# RMII_Dongle.net
KiCad netlist of a schematic drawn in Altium Designer
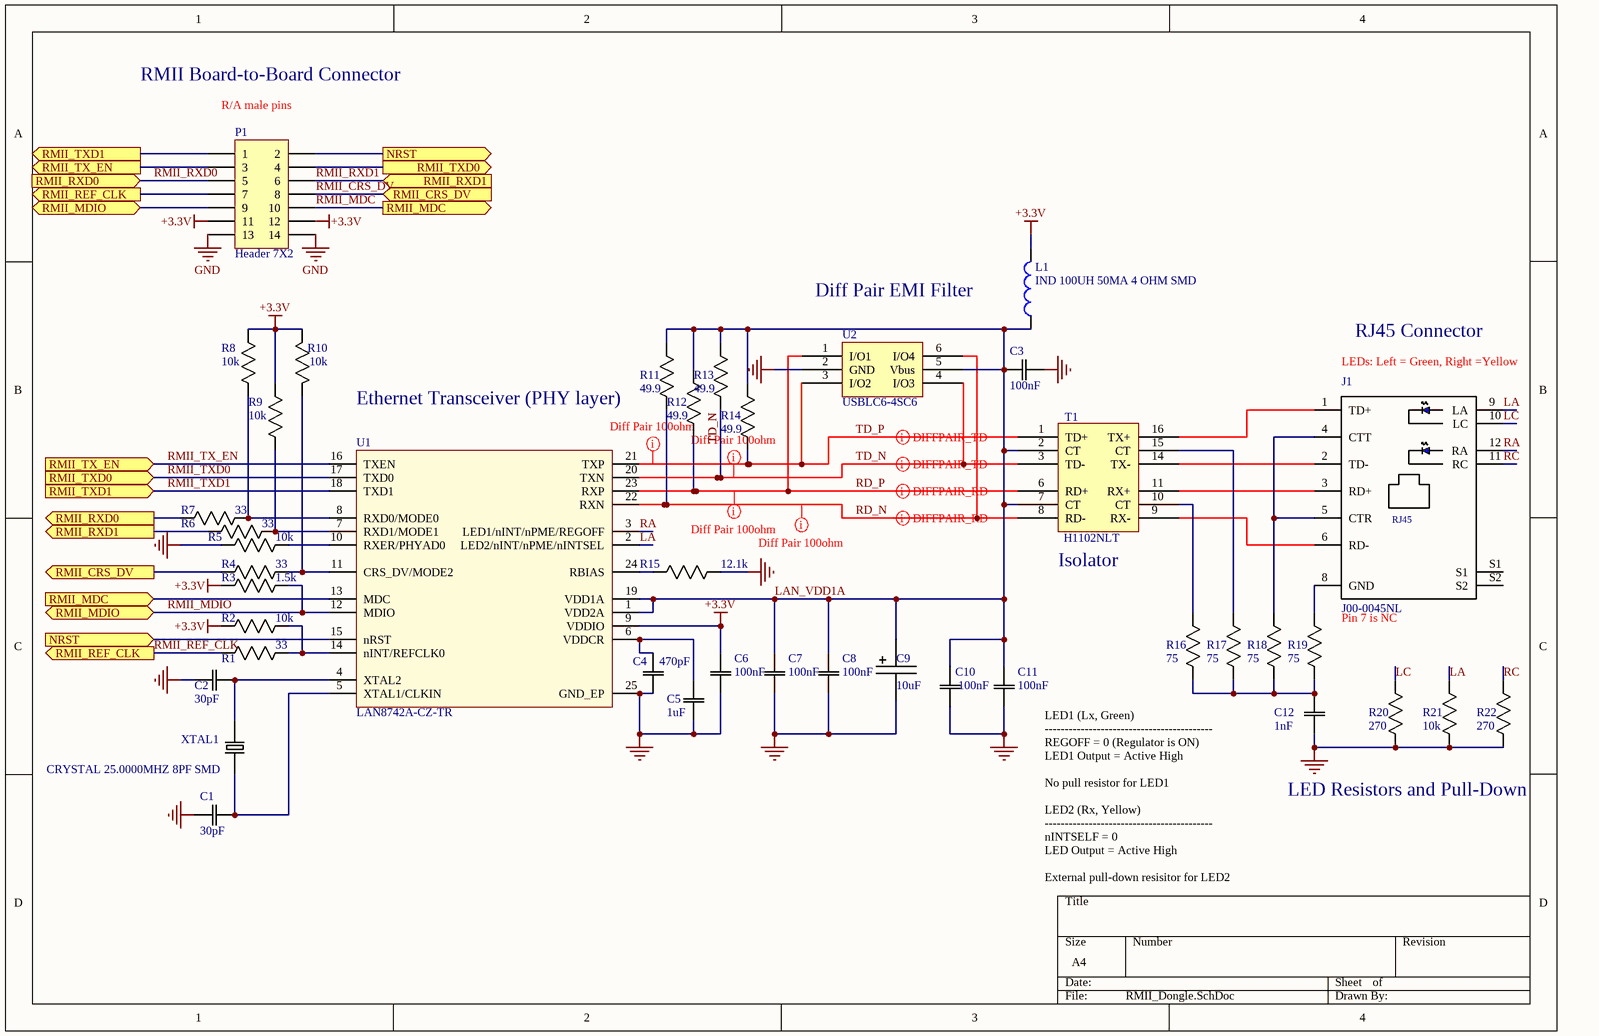
[diagram p0: RMII_Dongle.SchDoc]

(export (version "E")
  (design (tool "Eeschema 10.0.6"))
  (components
    (comp (ref "C1")
      (value "30pF")
      (footprint "0805")
      (description "CAP CER 30PF 25V NP0 0805")
      (fields (field (name "MP") "C0805C300M3GAC7800") (field (name "MF") "Yageo"))
      (libsource (lib "AltiumLibraries") (part "CAP 30pF 0805"))
    )
    (comp (ref "C2")
      (value "30pF")
      (footprint "0805")
      (description "CAP CER 30PF 25V NP0 0805")
      (fields (field (name "MP") "C0805C300M3GAC7800") (field (name "MF") "Yageo"))
      (libsource (lib "AltiumLibraries") (part "CAP 30pF 0805"))
    )
    (comp (ref "C3")
      (value "100nF")
      (footprint "0805")
      (description "CAP CER 0.1UF 50V X7R 0805")
      (fields (field (name "MP") "CC0805KRX7R9BB104") (field (name "MF") "Yageo"))
      (libsource (lib "AltiumLibraries") (part "CAP 100nF 0805"))
    )
    (comp (ref "C4")
      (value "470pF")
      (footprint "0805")
      (description "CAP CER 470PF 50V C0G/NPO 0805")
      (fields (field (name "MP") "CC0805JRNPO9BN471") (field (name "MF") "Yageo"))
      (libsource (lib "AltiumLibraries") (part "CAP 470pF 0805"))
    )
    (comp (ref "C5")
      (value "1uF")
      (footprint "0805")
      (description "CAP CER 1UF 50V X7R 0805")
      (fields (field (name "MP") "CL21B105KBFNNNE") (field (name "MF") "Samsung Electro-Mechanics"))
      (libsource (lib "AltiumLibraries") (part "CAP 1uF 0805"))
    )
    (comp (ref "C6")
      (value "100nF")
      (footprint "0805")
      (description "CAP CER 0.1UF 50V X7R 0805")
      (fields (field (name "MP") "CC0805KRX7R9BB104") (field (name "MF") "Yageo"))
      (libsource (lib "AltiumLibraries") (part "CAP 100nF 0805"))
    )
    (comp (ref "C7")
      (value "100nF")
      (footprint "0805")
      (description "CAP CER 0.1UF 50V X7R 0805")
      (fields (field (name "MP") "CC0805KRX7R9BB104") (field (name "MF") "Yageo"))
      (libsource (lib "AltiumLibraries") (part "CAP 100nF 0805"))
    )
    (comp (ref "C8")
      (value "100nF")
      (footprint "0805")
      (description "CAP CER 0.1UF 50V X7R 0805")
      (fields (field (name "MP") "CC0805KRX7R9BB104") (field (name "MF") "Yageo"))
      (libsource (lib "AltiumLibraries") (part "CAP 100nF 0805"))
    )
    (comp (ref "C9")
      (value "10uF")
      (footprint "1206 Polarized")
      (description "10µF Molded Tantalum Capacitors 10V 1206 (3216 Metric) 3.8Ohm")
      (fields (field (name "MP") "T491A106K010AT") (field (name "MF") "KEMET"))
      (libsource (lib "AltiumLibraries") (part "CAP TANT 10uF 1206"))
    )
    (comp (ref "C10")
      (value "100nF")
      (footprint "0805")
      (description "CAP CER 0.1UF 50V X7R 0805")
      (fields (field (name "MP") "CC0805KRX7R9BB104") (field (name "MF") "Yageo"))
      (libsource (lib "AltiumLibraries") (part "CAP 100nF 0805"))
    )
    (comp (ref "C11")
      (value "100nF")
      (footprint "0805")
      (description "CAP CER 0.1UF 50V X7R 0805")
      (fields (field (name "MP") "CC0805KRX7R9BB104") (field (name "MF") "Yageo"))
      (libsource (lib "AltiumLibraries") (part "CAP 100nF 0805"))
    )
    (comp (ref "C12")
      (value "1nF")
      (footprint "0805")
      (description "CAP CER 1000PF 50V X7R 0805")
      (fields (field (name "MP") "CC0805KRX7R9BB102") (field (name "MF") "Yageo"))
      (libsource (lib "AltiumLibraries") (part "CAP 1nF 0805"))
    )
    (comp (ref "J1")
      (value "J00-0045NL")
      (footprint "RJ45 J00-0045NL")
      (description "1 Port RJ45 Magjack Connector Through Hole 10/100 Base-TX, AutoMDIX")
      (fields (field (name "MF") "Pulse Electronics"))
      (libsource (lib "AltiumLibraries") (part "J00-0045NL"))
    )
    (comp (ref "L1")
      (value "IND 100UH 50MA 4 OHM SMD")
      (footprint "0805")
      (description "100µH Unshielded Wirewound Inductor 50mA 4Ohm 0805 (2012 Metric)")
      (fields (field (name "MF") "Taiyo Yuden") (field (name "MP") "LBR2012T101K"))
      (libsource (lib "AltiumLibraries") (part "IND 100UH 50MA 4 OHM SMD"))
    )
    (comp (ref "P1")
      (value "Header 7X2")
      (footprint "HDR2X7")
      (description "Header, 7-Pin, Dual row")
      (fields (field (name "PUBLISHER") "Altium Limited"))
      (libsource (lib "Miscellaneous Connectors") (part "Header 7X2"))
    )
    (comp (ref "R1")
      (value "33")
      (footprint "0805")
      (description "RES SMD 33 OHM 1% 1/8W 0805")
      (fields (field (name "MP") "RC0805FR-0733RL") (field (name "MF") "Yageo"))
      (libsource (lib "AltiumLibraries") (part "RES 33 0805"))
    )
    (comp (ref "R2")
      (value "10k")
      (footprint "0805")
      (description "RES SMD 10K OHM 1% 1/8W 0805")
      (fields (field (name "MP") "RC0805FR-0710KL") (field (name "MF") "Yageo"))
      (libsource (lib "") (part "RES 10k 0805_1"))
    )
    (comp (ref "R3")
      (value "1.5k")
      (footprint "0805")
      (description "RES SMD 1.5K OHM 1% 1/8W 0805")
      (fields (field (name "MP") "RC0805FR-071K5L") (field (name "MF") "Yageo"))
      (libsource (lib "AltiumLibraries") (part "RES 1.5k 0805"))
    )
    (comp (ref "R4")
      (value "33")
      (footprint "0805")
      (description "RES SMD 33 OHM 1% 1/8W 0805")
      (fields (field (name "MP") "RC0805FR-0733RL") (field (name "MF") "Yageo"))
      (libsource (lib "AltiumLibraries") (part "RES 33 0805"))
    )
    (comp (ref "R5")
      (value "10k")
      (footprint "0805")
      (description "RES SMD 10K OHM 1% 1/8W 0805")
      (fields (field (name "MP") "RC0805FR-0710KL") (field (name "MF") "Yageo"))
      (libsource (lib "") (part "RES 10k 0805_1"))
    )
    (comp (ref "R6")
      (value "33")
      (footprint "0805")
      (description "RES SMD 33 OHM 1% 1/8W 0805")
      (fields (field (name "MP") "RC0805FR-0733RL") (field (name "MF") "Yageo"))
      (libsource (lib "AltiumLibraries") (part "RES 33 0805"))
    )
    (comp (ref "R7")
      (value "33")
      (footprint "0805")
      (description "RES SMD 33 OHM 1% 1/8W 0805")
      (fields (field (name "MP") "RC0805FR-0733RL") (field (name "MF") "Yageo"))
      (libsource (lib "AltiumLibraries") (part "RES 33 0805"))
    )
    (comp (ref "R8")
      (value "10k")
      (footprint "0805")
      (description "RES SMD 10K OHM 1% 1/8W 0805")
      (fields (field (name "MP") "RC0805FR-0710KL") (field (name "MF") "Yageo"))
      (libsource (lib "AltiumLibraries") (part "RES 10k 0805"))
    )
    (comp (ref "R9")
      (value "10k")
      (footprint "0805")
      (description "RES SMD 10K OHM 1% 1/8W 0805")
      (fields (field (name "MP") "RC0805FR-0710KL") (field (name "MF") "Yageo"))
      (libsource (lib "AltiumLibraries") (part "RES 10k 0805"))
    )
    (comp (ref "R10")
      (value "10k")
      (footprint "0805")
      (description "RES SMD 10K OHM 1% 1/8W 0805")
      (fields (field (name "MP") "RC0805FR-0710KL") (field (name "MF") "Yageo"))
      (libsource (lib "AltiumLibraries") (part "RES 10k 0805"))
    )
    (comp (ref "R11")
      (value "49.9")
      (footprint "0805")
      (description "RES SMD 49.9 OHM 1% 1/8W 0805")
      (fields (field (name "MP") "RC0805FR-0749R9L") (field (name "MF") "Yageo"))
      (libsource (lib "AltiumLibraries") (part "RES 49.9 0805"))
    )
    (comp (ref "R12")
      (value "49.9")
      (footprint "0805")
      (description "RES SMD 49.9 OHM 1% 1/8W 0805")
      (fields (field (name "MP") "RC0805FR-0749R9L") (field (name "MF") "Yageo"))
      (libsource (lib "AltiumLibraries") (part "RES 49.9 0805"))
    )
    (comp (ref "R13")
      (value "49.9")
      (footprint "0805")
      (description "RES SMD 49.9 OHM 1% 1/8W 0805")
      (fields (field (name "MP") "RC0805FR-0749R9L") (field (name "MF") "Yageo"))
      (libsource (lib "AltiumLibraries") (part "RES 49.9 0805"))
    )
    (comp (ref "R14")
      (value "49.9")
      (footprint "0805")
      (description "RES SMD 49.9 OHM 1% 1/8W 0805")
      (fields (field (name "MP") "RC0805FR-0749R9L") (field (name "MF") "Yageo"))
      (libsource (lib "AltiumLibraries") (part "RES 49.9 0805"))
    )
    (comp (ref "R15")
      (value "12.1k")
      (footprint "0805")
      (description "RES SMD 12.1K OHM 1% 1/8W 0805")
      (fields (field (name "MP") "RC0805FR-0712K1L") (field (name "MF") "Yageo"))
      (libsource (lib "AltiumLibraries") (part "RES 12.1k 0805"))
    )
    (comp (ref "R16")
      (value "75")
      (footprint "0805")
      (description "RES SMD 75 OHM 1% 1/8W 0805")
      (fields (field (name "MP") "RC0805FR-0775RL") (field (name "MF") "Yageo"))
      (libsource (lib "AltiumLibraries") (part "RES 75 0805"))
    )
    (comp (ref "R17")
      (value "75")
      (footprint "0805")
      (description "RES SMD 75 OHM 1% 1/8W 0805")
      (fields (field (name "MP") "RC0805FR-0775RL") (field (name "MF") "Yageo"))
      (libsource (lib "AltiumLibraries") (part "RES 75 0805"))
    )
    (comp (ref "R18")
      (value "75")
      (footprint "0805")
      (description "RES SMD 75 OHM 1% 1/8W 0805")
      (fields (field (name "MP") "RC0805FR-0775RL") (field (name "MF") "Yageo"))
      (libsource (lib "AltiumLibraries") (part "RES 75 0805"))
    )
    (comp (ref "R19")
      (value "75")
      (footprint "0805")
      (description "RES SMD 75 OHM 1% 1/8W 0805")
      (fields (field (name "MP") "RC0805FR-0775RL") (field (name "MF") "Yageo"))
      (libsource (lib "AltiumLibraries") (part "RES 75 0805"))
    )
    (comp (ref "R20")
      (value "270")
      (footprint "0805")
      (description "RES SMD 270 OHM 5% 1/8W 0805")
      (fields (field (name "MP") "RC0805JR-07270RL") (field (name "MF") "Yageo"))
      (libsource (lib "AltiumLibraries") (part "RES 270 0805"))
    )
    (comp (ref "R21")
      (value "10k")
      (footprint "0805")
      (description "RES SMD 10K OHM 1% 1/8W 0805")
      (fields (field (name "MP") "RC0805FR-0710KL") (field (name "MF") "Yageo"))
      (libsource (lib "AltiumLibraries") (part "RES 10k 0805"))
    )
    (comp (ref "R22")
      (value "270")
      (footprint "0805")
      (description "RES SMD 270 OHM 5% 1/8W 0805")
      (fields (field (name "MP") "RC0805JR-07270RL") (field (name "MF") "Yageo"))
      (libsource (lib "AltiumLibraries") (part "RES 270 0805"))
    )
    (comp (ref "T1")
      (value "H1102NLT")
      (footprint "TRANSFORMER")
      (fields (field (name "MF") "Pulse Electronics") (field (name "MP") "H1102NL"))
      (libsource (lib "AltiumLibraries") (part "H1102NLT"))
    )
    (comp (ref "U1")
      (value "LAN8742A-CZ-TR")
      (footprint "24-QFN (4x4)")
      (fields (field (name "MF") "Microchip Technology"))
      (libsource (lib "AltiumLibraries") (part "LAN8742A-CZ-TR"))
    )
    (comp (ref "U2")
      (value "USBLC6-4SC6")
      (footprint "SOT23-6L")
      (libsource (lib "AltiumLibraries") (part "USBLC6-4SC6"))
    )
    (comp (ref "XTAL1")
      (value "CRYSTAL 25.0000MHZ 8PF SMD")
      (footprint "SMD-2")
      (description "25MHz ±50ppm Crystal 8pF 70 Ohms 2-SMD, No Lead")
      (fields (field (name "MP") "NX5032GA-25.000000MHZ-LN-CD-1") (field (name "MF") "NDK America, Inc."))
      (libsource (lib "AltiumLibraries") (part "XTAL 25MHZ 8PF SMD"))
    )
  )
  (nets
    (net (code "1") (name "+3.3V") (class "Default")
      (node (ref "C6") (pin "2") (pinfunction "C2_2") (pintype "passive"))
      (node (ref "L1") (pin "2") (pinfunction "2_2") (pintype "passive"))
      (node (ref "P1") (pin "11") (pinfunction "11_11") (pintype "passive"))
      (node (ref "P1") (pin "12") (pinfunction "12_12") (pintype "passive"))
      (node (ref "R10") (pin "1") (pinfunction "R1_1") (pintype "passive"))
      (node (ref "R2") (pin "2") (pinfunction "R2_2") (pintype "passive"))
      (node (ref "R3") (pin "2") (pinfunction "R2_2") (pintype "passive"))
      (node (ref "R8") (pin "1") (pinfunction "R1_1") (pintype "passive"))
      (node (ref "R9") (pin "1") (pinfunction "R1_1") (pintype "passive"))
      (node (ref "U1") (pin "9") (pinfunction "VDDIO_9") (pintype "passive"))
    )
    (net (code "2") (name "/LA") (class "Default")
      (node (ref "J1") (pin "9") (pinfunction "LA_9") (pintype "passive"))
      (node (ref "R21") (pin "1") (pinfunction "R1_1") (pintype "passive"))
      (node (ref "U1") (pin "2") (pinfunction "LED2/nINT/nPME/nINTSEL_2") (pintype "passive"))
    )
    (net (code "3") (name "/LAN_VDD1A") (class "Default")
      (node (ref "C10") (pin "2") (pinfunction "C2_2") (pintype "passive"))
      (node (ref "C11") (pin "2") (pinfunction "C2_2") (pintype "passive"))
      (node (ref "C3") (pin "1") (pinfunction "C1_1") (pintype "passive"))
      (node (ref "C7") (pin "2") (pinfunction "C2_2") (pintype "passive"))
      (node (ref "C8") (pin "2") (pinfunction "C2_2") (pintype "passive"))
      (node (ref "C9") (pin "1") (pinfunction "P$1_1") (pintype "passive"))
      (node (ref "L1") (pin "1") (pinfunction "1_1") (pintype "passive"))
      (node (ref "R11") (pin "1") (pinfunction "R1_1") (pintype "passive"))
      (node (ref "R12") (pin "1") (pinfunction "R1_1") (pintype "passive"))
      (node (ref "R13") (pin "1") (pinfunction "R1_1") (pintype "passive"))
      (node (ref "R14") (pin "1") (pinfunction "R1_1") (pintype "passive"))
      (node (ref "T1") (pin "2") (pinfunction "CT_2") (pintype "passive"))
      (node (ref "T1") (pin "7") (pinfunction "CT_7") (pintype "passive"))
      (node (ref "U1") (pin "1") (pinfunction "VDD2A_1") (pintype "passive"))
      (node (ref "U1") (pin "19") (pinfunction "VDD1A_19") (pintype "passive"))
      (node (ref "U2") (pin "5") (pinfunction "Vbus_5") (pintype "passive"))
    )
    (net (code "4") (name "/LC") (class "Default")
      (node (ref "J1") (pin "10") (pinfunction "LC_10") (pintype "passive"))
      (node (ref "R20") (pin "1") (pinfunction "R1_1") (pintype "passive"))
    )
    (net (code "5") (name "/NRST") (class "Default")
      (node (ref "P1") (pin "2") (pinfunction "2_2") (pintype "passive"))
      (node (ref "U1") (pin "15") (pinfunction "nRST_15") (pintype "passive"))
    )
    (net (code "6") (name "/RA") (class "Default")
      (node (ref "J1") (pin "12") (pinfunction "RA_12") (pintype "passive"))
      (node (ref "U1") (pin "3") (pinfunction "LED1/nINT/nPME/REGOFF_3") (pintype "passive"))
    )
    (net (code "7") (name "/RC") (class "Default")
      (node (ref "J1") (pin "11") (pinfunction "RC_11") (pintype "passive"))
      (node (ref "R22") (pin "1") (pinfunction "R1_1") (pintype "passive"))
    )
    (net (code "8") (name "/RD_N") (class "Default")
      (node (ref "R11") (pin "2") (pinfunction "R2_2") (pintype "passive"))
      (node (ref "T1") (pin "8") (pinfunction "RD-_8") (pintype "passive"))
      (node (ref "U1") (pin "22") (pinfunction "RXN_22") (pintype "passive"))
      (node (ref "U2") (pin "6") (pinfunction "I/O4_6") (pintype "passive"))
    )
    (net (code "9") (name "/RD_P") (class "Default")
      (node (ref "R12") (pin "2") (pinfunction "R2_2") (pintype "passive"))
      (node (ref "T1") (pin "6") (pinfunction "RD+_6") (pintype "passive"))
      (node (ref "U1") (pin "23") (pinfunction "RXP_23") (pintype "passive"))
      (node (ref "U2") (pin "1") (pinfunction "I/O1_1") (pintype "passive"))
    )
    (net (code "10") (name "/RMII_CRS_DV") (class "Default")
      (node (ref "P1") (pin "8") (pinfunction "8_8") (pintype "passive"))
      (node (ref "R4") (pin "2") (pinfunction "R2_2") (pintype "passive"))
    )
    (net (code "11") (name "/RMII_MDC") (class "Default")
      (node (ref "P1") (pin "10") (pinfunction "10_10") (pintype "passive"))
      (node (ref "U1") (pin "13") (pinfunction "MDC_13") (pintype "passive"))
    )
    (net (code "12") (name "/RMII_MDIO") (class "Default")
      (node (ref "P1") (pin "9") (pinfunction "9_9") (pintype "passive"))
      (node (ref "R3") (pin "1") (pinfunction "R1_1") (pintype "passive"))
      (node (ref "U1") (pin "12") (pinfunction "MDIO_12") (pintype "passive"))
    )
    (net (code "13") (name "/RMII_REF_CLK") (class "Default")
      (node (ref "P1") (pin "7") (pinfunction "7_7") (pintype "passive"))
      (node (ref "R1") (pin "2") (pinfunction "R2_2") (pintype "passive"))
    )
    (net (code "14") (name "/RMII_RXD0") (class "Default")
      (node (ref "P1") (pin "5") (pinfunction "5_5") (pintype "passive"))
      (node (ref "R7") (pin "2") (pinfunction "R2_2") (pintype "passive"))
    )
    (net (code "15") (name "/RMII_RXD1") (class "Default")
      (node (ref "P1") (pin "6") (pinfunction "6_6") (pintype "passive"))
      (node (ref "R6") (pin "2") (pinfunction "R2_2") (pintype "passive"))
    )
    (net (code "16") (name "/RMII_TXD0") (class "Default")
      (node (ref "P1") (pin "4") (pinfunction "4_4") (pintype "passive"))
      (node (ref "U1") (pin "17") (pinfunction "TXD0_17") (pintype "passive"))
    )
    (net (code "17") (name "/RMII_TXD1") (class "Default")
      (node (ref "P1") (pin "1") (pinfunction "1_1") (pintype "passive"))
      (node (ref "U1") (pin "18") (pinfunction "TXD1_18") (pintype "passive"))
    )
    (net (code "18") (name "/RMII_TX_EN") (class "Default")
      (node (ref "P1") (pin "3") (pinfunction "3_3") (pintype "passive"))
      (node (ref "U1") (pin "16") (pinfunction "TXEN_16") (pintype "passive"))
    )
    (net (code "19") (name "/TD_N") (class "Default")
      (node (ref "R13") (pin "2") (pinfunction "R2_2") (pintype "passive"))
      (node (ref "T1") (pin "3") (pinfunction "TD-_3") (pintype "passive"))
      (node (ref "U1") (pin "20") (pinfunction "TXN_20") (pintype "passive"))
      (node (ref "U2") (pin "4") (pinfunction "I/O3_4") (pintype "passive"))
    )
    (net (code "20") (name "/TD_P") (class "Default")
      (node (ref "R14") (pin "2") (pinfunction "R2_2") (pintype "passive"))
      (node (ref "T1") (pin "1") (pinfunction "TD+_1") (pintype "passive"))
      (node (ref "U1") (pin "21") (pinfunction "TXP_21") (pintype "passive"))
      (node (ref "U2") (pin "3") (pinfunction "I/O2_3") (pintype "passive"))
    )
    (net (code "21") (name "GND") (class "Default")
      (node (ref "C1") (pin "1") (pinfunction "C1_1") (pintype "passive"))
      (node (ref "C10") (pin "1") (pinfunction "C1_1") (pintype "passive"))
      (node (ref "C11") (pin "1") (pinfunction "C1_1") (pintype "passive"))
      (node (ref "C12") (pin "1") (pinfunction "C1_1") (pintype "passive"))
      (node (ref "C2") (pin "1") (pinfunction "C1_1") (pintype "passive"))
      (node (ref "C3") (pin "2") (pinfunction "C2_2") (pintype "passive"))
      (node (ref "C4") (pin "1") (pinfunction "C1_1") (pintype "passive"))
      (node (ref "C5") (pin "1") (pinfunction "C1_1") (pintype "passive"))
      (node (ref "C6") (pin "1") (pinfunction "C1_1") (pintype "passive"))
      (node (ref "C7") (pin "1") (pinfunction "C1_1") (pintype "passive"))
      (node (ref "C8") (pin "1") (pinfunction "C1_1") (pintype "passive"))
      (node (ref "C9") (pin "2") (pinfunction "P$2_2") (pintype "passive"))
      (node (ref "P1") (pin "13") (pinfunction "13_13") (pintype "passive"))
      (node (ref "P1") (pin "14") (pinfunction "14_14") (pintype "passive"))
      (node (ref "R15") (pin "1") (pinfunction "R1_1") (pintype "passive"))
      (node (ref "R20") (pin "2") (pinfunction "R2_2") (pintype "passive"))
      (node (ref "R21") (pin "2") (pinfunction "R2_2") (pintype "passive"))
      (node (ref "R22") (pin "2") (pinfunction "R2_2") (pintype "passive"))
      (node (ref "R5") (pin "2") (pinfunction "R2_2") (pintype "passive"))
      (node (ref "U1") (pin "25") (pinfunction "GND_EP_25") (pintype "passive"))
      (node (ref "U2") (pin "2") (pinfunction "GND_2") (pintype "passive"))
    )
    (net (code "22") (name "Net-(C1-C2)") (class "Default")
      (node (ref "C1") (pin "2") (pinfunction "C2_2") (pintype "passive"))
      (node (ref "U1") (pin "5") (pinfunction "XTAL1/CLKIN_5") (pintype "passive"))
      (node (ref "XTAL1") (pin "1") (pinfunction "1_1") (pintype "passive"))
    )
    (net (code "23") (name "Net-(C2-C2)") (class "Default")
      (node (ref "C2") (pin "2") (pinfunction "C2_2") (pintype "passive"))
      (node (ref "U1") (pin "4") (pinfunction "XTAL2_4") (pintype "passive"))
      (node (ref "XTAL1") (pin "2") (pinfunction "2_2") (pintype "passive"))
    )
    (net (code "24") (name "Net-(C4-C2)") (class "Default")
      (node (ref "C4") (pin "2") (pinfunction "C2_2") (pintype "passive"))
      (node (ref "C5") (pin "2") (pinfunction "C2_2") (pintype "passive"))
      (node (ref "U1") (pin "6") (pinfunction "VDDCR_6") (pintype "passive"))
    )
    (net (code "25") (name "Net-(C12-C2)") (class "Default")
      (node (ref "C12") (pin "2") (pinfunction "C2_2") (pintype "passive"))
      (node (ref "R16") (pin "2") (pinfunction "R2_2") (pintype "passive"))
      (node (ref "R17") (pin "2") (pinfunction "R2_2") (pintype "passive"))
      (node (ref "R18") (pin "2") (pinfunction "R2_2") (pintype "passive"))
      (node (ref "R19") (pin "2") (pinfunction "R2_2") (pintype "passive"))
    )
    (net (code "26") (name "Net-(J1-CTR)") (class "Default")
      (node (ref "J1") (pin "4") (pinfunction "CTT_4") (pintype "passive"))
      (node (ref "J1") (pin "5") (pinfunction "CTR_5") (pintype "passive"))
      (node (ref "R18") (pin "1") (pinfunction "R1_1") (pintype "passive"))
    )
    (net (code "27") (name "Net-(J1-GND)") (class "Default")
      (node (ref "J1") (pin "8") (pinfunction "GND_8") (pintype "passive"))
      (node (ref "R19") (pin "1") (pinfunction "R1_1") (pintype "passive"))
    )
    (net (code "28") (name "Net-(J1-RD+)") (class "Default")
      (node (ref "J1") (pin "3") (pinfunction "RD+_3") (pintype "passive"))
      (node (ref "T1") (pin "11") (pinfunction "RX+_11") (pintype "passive"))
    )
    (net (code "29") (name "Net-(J1-RD-)") (class "Default")
      (node (ref "J1") (pin "6") (pinfunction "RD-_6") (pintype "passive"))
      (node (ref "T1") (pin "9") (pinfunction "RX-_9") (pintype "passive"))
    )
    (net (code "30") (name "Net-(J1-TD+)") (class "Default")
      (node (ref "J1") (pin "1") (pinfunction "TD+_1") (pintype "passive"))
      (node (ref "T1") (pin "16") (pinfunction "TX+_16") (pintype "passive"))
    )
    (net (code "31") (name "Net-(J1-TD-)") (class "Default")
      (node (ref "J1") (pin "2") (pinfunction "TD-_2") (pintype "passive"))
      (node (ref "T1") (pin "14") (pinfunction "TX-_14") (pintype "passive"))
    )
    (net (code "32") (name "Net-(R1-R1)") (class "Default")
      (node (ref "R1") (pin "1") (pinfunction "R1_1") (pintype "passive"))
      (node (ref "R2") (pin "1") (pinfunction "R1_1") (pintype "passive"))
      (node (ref "U1") (pin "14") (pinfunction "nINT/REFCLK0_14") (pintype "passive"))
    )
    (net (code "33") (name "Net-(R5-R1)") (class "Default")
      (node (ref "R5") (pin "1") (pinfunction "R1_1") (pintype "passive"))
      (node (ref "U1") (pin "10") (pinfunction "RXER/PHYAD0_10") (pintype "passive"))
    )
    (net (code "34") (name "Net-(R6-R1)") (class "Default")
      (node (ref "R6") (pin "1") (pinfunction "R1_1") (pintype "passive"))
      (node (ref "R9") (pin "2") (pinfunction "R2_2") (pintype "passive"))
      (node (ref "U1") (pin "7") (pinfunction "RXD1/MODE1_7") (pintype "passive"))
    )
    (net (code "35") (name "Net-(R7-R1)") (class "Default")
      (node (ref "R7") (pin "1") (pinfunction "R1_1") (pintype "passive"))
      (node (ref "R8") (pin "2") (pinfunction "R2_2") (pintype "passive"))
      (node (ref "U1") (pin "8") (pinfunction "RXD0/MODE0_8") (pintype "passive"))
    )
    (net (code "36") (name "Net-(R10-R2)") (class "Default")
      (node (ref "R10") (pin "2") (pinfunction "R2_2") (pintype "passive"))
      (node (ref "R4") (pin "1") (pinfunction "R1_1") (pintype "passive"))
      (node (ref "U1") (pin "11") (pinfunction "CRS_DV/MODE2_11") (pintype "passive"))
    )
    (net (code "37") (name "Net-(R15-R2)") (class "Default")
      (node (ref "R15") (pin "2") (pinfunction "R2_2") (pintype "passive"))
      (node (ref "U1") (pin "24") (pinfunction "RBIAS_24") (pintype "passive"))
    )
    (net (code "38") (name "Net-(R16-R1)") (class "Default")
      (node (ref "R16") (pin "1") (pinfunction "R1_1") (pintype "passive"))
      (node (ref "T1") (pin "10") (pinfunction "CT_10") (pintype "passive"))
    )
    (net (code "39") (name "Net-(R17-R1)") (class "Default")
      (node (ref "R17") (pin "1") (pinfunction "R1_1") (pintype "passive"))
      (node (ref "T1") (pin "15") (pinfunction "CT_15") (pintype "passive"))
    )
    (net (code "40") (name "unconnected-(J1-PadS1)") (class "Default")
      (node (ref "J1") (pin "S1") (pinfunction "S1_S1") (pintype "passive"))
    )
    (net (code "41") (name "unconnected-(J1-PadS2)") (class "Default")
      (node (ref "J1") (pin "S2") (pinfunction "S2_S2") (pintype "passive"))
    )
  )
)
